# sterowanie.net
KiCad netlist of a schematic drawn in EAGLE
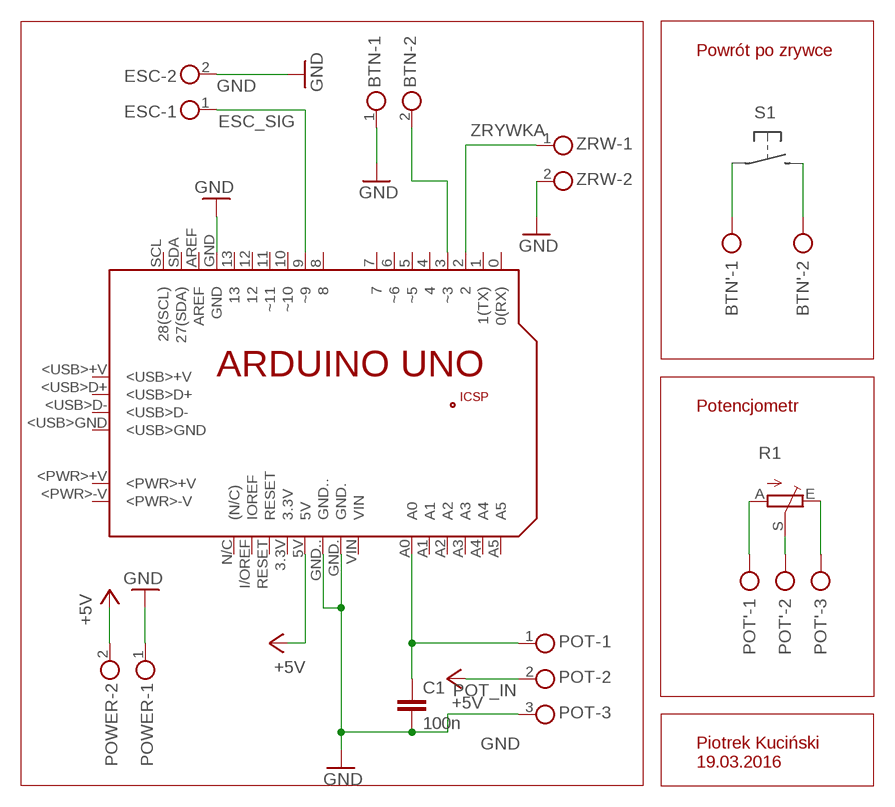
[diagram p0: schematic, sheet 1]

(export (version "E")
  (design (tool "Eeschema 10.0.6"))
  (components
    (comp (ref "BTN")
      (value "AKL59-02")
      (footprint "eagle-import:2POL35")
      (libsource (lib "eagle-import") (part "AKL59-02"))
    )
    (comp (ref "BTN'")
      (value "AK300/2")
      (footprint "eagle-import:AK300_2")
      (libsource (lib "eagle-import") (part "AK300/2"))
    )
    (comp (ref "C1")
      (value "100n")
      (footprint "eagle-import:C1206")
      (libsource (lib "eagle-import") (part "C-EUC1206"))
    )
    (comp (ref "ESC")
      (value "AKL59-02")
      (footprint "eagle-import:2POL35")
      (libsource (lib "eagle-import") (part "AKL59-02"))
    )
    (comp (ref "PCB1")
      (value "ARDUINO_UNO")
      (footprint "eagle-import:ARDUINO_UNO")
      (libsource (lib "eagle-import") (part "ARDUINO_UNO"))
    )
    (comp (ref "POT")
      (value "AKL59-03")
      (footprint "eagle-import:3POL35")
      (libsource (lib "eagle-import") (part "AKL59-03"))
    )
    (comp (ref "POT'")
      (value "AK300/3")
      (footprint "eagle-import:AK300_3")
      (libsource (lib "eagle-import") (part "AK300/3"))
    )
    (comp (ref "POWER")
      (value "AKL59-02")
      (footprint "eagle-import:2POL35")
      (libsource (lib "eagle-import") (part "AKL59-02"))
    )
    (comp (ref "R1")
      (value "TRIM_EU-B90P")
      (footprint "eagle-import:SP19L")
      (libsource (lib "eagle-import") (part "TRIM_EU-B90P"))
    )
    (comp (ref "ZRW")
      (value "AKL59-02")
      (footprint "eagle-import:2POL35")
      (libsource (lib "eagle-import") (part "AKL59-02"))
    )
  )
  (nets
    (net (code "1") (name "+5V") (class "Default")
      (node (ref "PCB1") (pin "5V") (pinfunction "5V_5V") (pintype "bidirectional"))
      (node (ref "POT") (pin "2") (pinfunction "1_2") (pintype "passive"))
      (node (ref "POWER") (pin "2") (pinfunction "1_2") (pintype "passive"))
    )
    (net (code "2") (name "/ESC_SIG") (class "Default")
      (node (ref "ESC") (pin "1") (pinfunction "1_1") (pintype "passive"))
      (node (ref "PCB1") (pin "9") (pinfunction "~{9}_9") (pintype "bidirectional"))
    )
    (net (code "3") (name "/POT_IN") (class "Default")
      (node (ref "C1") (pin "1") (pinfunction "1_1") (pintype "passive"))
      (node (ref "PCB1") (pin "A0") (pinfunction "A0_A0") (pintype "bidirectional"))
      (node (ref "POT") (pin "1") (pinfunction "1_1") (pintype "passive"))
    )
    (net (code "4") (name "/ZRYWKA") (class "Default")
      (node (ref "PCB1") (pin "2") (pinfunction "2_2") (pintype "bidirectional"))
      (node (ref "ZRW") (pin "1") (pinfunction "1_1") (pintype "passive"))
    )
    (net (code "5") (name "GND") (class "Default")
      (node (ref "BTN") (pin "1") (pinfunction "1_1") (pintype "passive"))
      (node (ref "C1") (pin "2") (pinfunction "2_2") (pintype "passive"))
      (node (ref "ESC") (pin "2") (pinfunction "1_2") (pintype "passive"))
      (node (ref "PCB1") (pin "GND") (pinfunction "GND_GND") (pintype "bidirectional"))
      (node (ref "PCB1") (pin "GND.") (pinfunction "GND._GND.") (pintype "bidirectional"))
      (node (ref "PCB1") (pin "GND..") (pinfunction "GND.._GND..") (pintype "bidirectional"))
      (node (ref "POT") (pin "3") (pinfunction "1_3") (pintype "passive"))
      (node (ref "POWER") (pin "1") (pinfunction "1_1") (pintype "passive"))
      (node (ref "ZRW") (pin "2") (pinfunction "1_2") (pintype "passive"))
    )
    (net (code "6") (name "Net-(BTNB-1)") (class "Default")
      (node (ref "BTN") (pin "2") (pinfunction "1_2") (pintype "passive"))
      (node (ref "PCB1") (pin "3") (pinfunction "~{3}_3") (pintype "bidirectional"))
    )
    (net (code "7") (name "Net-(POT'A-KL)") (class "Default")
      (node (ref "POT'") (pin "1") (pinfunction "KL_1") (pintype "passive"))
      (node (ref "R1") (pin "A") (pinfunction "A_A") (pintype "passive"))
    )
    (net (code "8") (name "Net-(POT'B-KL)") (class "Default")
      (node (ref "POT'") (pin "2") (pinfunction "KL_2") (pintype "passive"))
      (node (ref "R1") (pin "S") (pinfunction "S_S") (pintype "passive"))
    )
    (net (code "9") (name "Net-(POT'C-KL)") (class "Default")
      (node (ref "POT'") (pin "3") (pinfunction "KL_3") (pintype "passive"))
      (node (ref "R1") (pin "E") (pinfunction "E_E") (pintype "passive"))
    )
    (net (code "10") (name "unconnected-(BTN'A-KL-Pad1)") (class "Default")
      (node (ref "BTN'") (pin "1") (pinfunction "KL_1") (pintype "passive"))
    )
    (net (code "11") (name "unconnected-(BTN'B-KL-Pad2)") (class "Default")
      (node (ref "BTN'") (pin "2") (pinfunction "KL_2") (pintype "passive"))
    )
    (net (code "12") (name "unconnected-(PCB1-(N{slash}C)-PadN{slash}C)") (class "Default")
      (node (ref "PCB1") (pin "N/C") (pinfunction "(N/C)_N/C") (pintype "bidirectional"))
    )
    (net (code "13") (name "unconnected-(PCB1-0(RX)-Pad0)") (class "Default")
      (node (ref "PCB1") (pin "0") (pinfunction "0(RX)_0") (pintype "bidirectional"))
    )
    (net (code "14") (name "unconnected-(PCB1-1(TX)-Pad1)") (class "Default")
      (node (ref "PCB1") (pin "1") (pinfunction "1(TX)_1") (pintype "bidirectional"))
    )
    (net (code "15") (name "unconnected-(PCB1-27(SDA)-PadSDA)") (class "Default")
      (node (ref "PCB1") (pin "SDA") (pinfunction "27(SDA)_SDA") (pintype "bidirectional"))
    )
    (net (code "16") (name "unconnected-(PCB1-28(SCL)-PadSCL)") (class "Default")
      (node (ref "PCB1") (pin "SCL") (pinfunction "28(SCL)_SCL") (pintype "bidirectional"))
    )
    (net (code "17") (name "unconnected-(PCB1-IOREF-PadI{slash}OREF)") (class "Default")
      (node (ref "PCB1") (pin "I/OREF") (pinfunction "IOREF_I/OREF") (pintype "bidirectional"))
    )
    (net (code "18") (name "unconnected-(PCB1-Pad+5V)") (class "Default")
      (node (ref "PCB1") (pin "+5V") (pinfunction "+5V_+5V") (pintype "bidirectional"))
    )
    (net (code "19") (name "unconnected-(PCB1-Pad3.3V)") (class "Default")
      (node (ref "PCB1") (pin "3.3V") (pinfunction "3.3V_3.3V") (pintype "bidirectional"))
    )
    (net (code "20") (name "unconnected-(PCB1-Pad4)") (class "Default")
      (node (ref "PCB1") (pin "4") (pinfunction "4_4") (pintype "bidirectional"))
    )
    (net (code "21") (name "unconnected-(PCB1-Pad7)") (class "Default")
      (node (ref "PCB1") (pin "7") (pinfunction "7_7") (pintype "bidirectional"))
    )
    (net (code "22") (name "unconnected-(PCB1-Pad8)") (class "Default")
      (node (ref "PCB1") (pin "8") (pinfunction "8_8") (pintype "bidirectional"))
    )
    (net (code "23") (name "unconnected-(PCB1-Pad12)") (class "Default")
      (node (ref "PCB1") (pin "12") (pinfunction "12_12") (pintype "bidirectional"))
    )
    (net (code "24") (name "unconnected-(PCB1-Pad13)") (class "Default")
      (node (ref "PCB1") (pin "13") (pinfunction "13_13") (pintype "bidirectional"))
    )
    (net (code "25") (name "unconnected-(PCB1-Pad<PWR>+V)") (class "Default")
      (node (ref "PCB1") (pin "<PWR>+V") (pinfunction "<PWR>+V_<PWR>+V") (pintype "bidirectional"))
    )
    (net (code "26") (name "unconnected-(PCB1-Pad<PWR>-V)") (class "Default")
      (node (ref "PCB1") (pin "<PWR>-V") (pinfunction "<PWR>-V_<PWR>-V") (pintype "bidirectional"))
    )
    (net (code "27") (name "unconnected-(PCB1-Pad<USB>+V)") (class "Default")
      (node (ref "PCB1") (pin "<USB>+V") (pinfunction "<USB>+V_<USB>+V") (pintype "bidirectional"))
    )
    (net (code "28") (name "unconnected-(PCB1-Pad<USB>D+)") (class "Default")
      (node (ref "PCB1") (pin "<USB>D+") (pinfunction "<USB>D+_<USB>D+") (pintype "bidirectional"))
    )
    (net (code "29") (name "unconnected-(PCB1-Pad<USB>D-)") (class "Default")
      (node (ref "PCB1") (pin "<USB>D-") (pinfunction "<USB>D-_<USB>D-") (pintype "bidirectional"))
    )
    (net (code "30") (name "unconnected-(PCB1-Pad<USB>GND)") (class "Default")
      (node (ref "PCB1") (pin "<USB>GND") (pinfunction "<USB>GND_<USB>GND") (pintype "bidirectional"))
    )
    (net (code "31") (name "unconnected-(PCB1-PadA1)") (class "Default")
      (node (ref "PCB1") (pin "A1") (pinfunction "A1_A1") (pintype "bidirectional"))
    )
    (net (code "32") (name "unconnected-(PCB1-PadA2)") (class "Default")
      (node (ref "PCB1") (pin "A2") (pinfunction "A2_A2") (pintype "bidirectional"))
    )
    (net (code "33") (name "unconnected-(PCB1-PadA3)") (class "Default")
      (node (ref "PCB1") (pin "A3") (pinfunction "A3_A3") (pintype "bidirectional"))
    )
    (net (code "34") (name "unconnected-(PCB1-PadA4)") (class "Default")
      (node (ref "PCB1") (pin "A4") (pinfunction "A4_A4") (pintype "bidirectional"))
    )
    (net (code "35") (name "unconnected-(PCB1-PadA5)") (class "Default")
      (node (ref "PCB1") (pin "A5") (pinfunction "A5_A5") (pintype "bidirectional"))
    )
    (net (code "36") (name "unconnected-(PCB1-PadAREF)") (class "Default")
      (node (ref "PCB1") (pin "AREF") (pinfunction "AREF_AREF") (pintype "bidirectional"))
    )
    (net (code "37") (name "unconnected-(PCB1-PadGND_)") (class "Default")
      (node (ref "PCB1") (pin "GND_") (pinfunction "GND__GND_") (pintype "bidirectional"))
    )
    (net (code "38") (name "unconnected-(PCB1-PadMISO)") (class "Default")
      (node (ref "PCB1") (pin "MISO") (pinfunction "MISO_MISO") (pintype "bidirectional"))
    )
    (net (code "39") (name "unconnected-(PCB1-PadMOSI)") (class "Default")
      (node (ref "PCB1") (pin "MOSI") (pinfunction "MOSI_MOSI") (pintype "bidirectional"))
    )
    (net (code "40") (name "unconnected-(PCB1-PadRESET)") (class "Default")
      (node (ref "PCB1") (pin "RESET") (pinfunction "RESET_RESET") (pintype "bidirectional"))
    )
    (net (code "41") (name "unconnected-(PCB1-PadRESET.)") (class "Default")
      (node (ref "PCB1") (pin "RESET.") (pinfunction "RESET._RESET.") (pintype "bidirectional"))
    )
    (net (code "42") (name "unconnected-(PCB1-PadSCK)") (class "Default")
      (node (ref "PCB1") (pin "SCK") (pinfunction "SCK_SCK") (pintype "bidirectional"))
    )
    (net (code "43") (name "unconnected-(PCB1-PadVIN)") (class "Default")
      (node (ref "PCB1") (pin "VIN") (pinfunction "VIN_VIN") (pintype "bidirectional"))
    )
    (net (code "44") (name "unconnected-(PCB1-~{5}-Pad5)") (class "Default")
      (node (ref "PCB1") (pin "5") (pinfunction "~{5}_5") (pintype "bidirectional"))
    )
    (net (code "45") (name "unconnected-(PCB1-~{6}-Pad6)") (class "Default")
      (node (ref "PCB1") (pin "6") (pinfunction "~{6}_6") (pintype "bidirectional"))
    )
    (net (code "46") (name "unconnected-(PCB1-~{10}-Pad10)") (class "Default")
      (node (ref "PCB1") (pin "10") (pinfunction "~{10}_10") (pintype "bidirectional"))
    )
    (net (code "47") (name "unconnected-(PCB1-~{11}-Pad11)") (class "Default")
      (node (ref "PCB1") (pin "11") (pinfunction "~{11}_11") (pintype "bidirectional"))
    )
  )
)
